# Connectors.net
KiCad netlist of a schematic drawn in Altium Designer
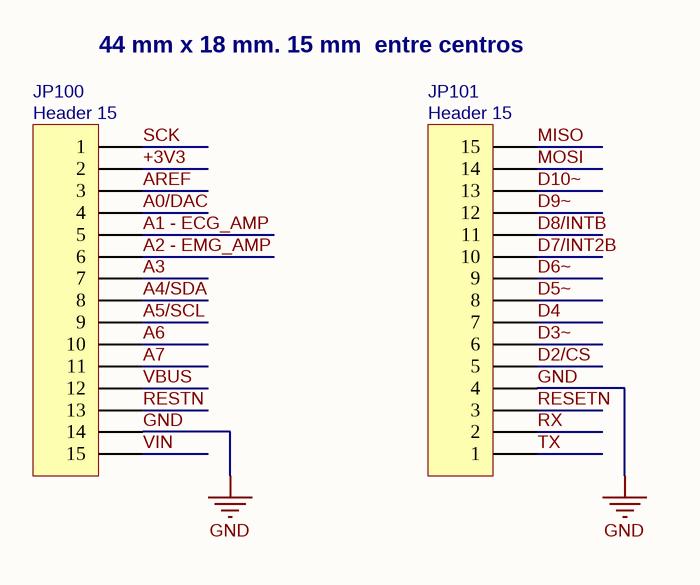
[diagram p0: Connectors.SchDoc]

(export (version "E")
  (design (tool "Eeschema 10.0.6"))
  (components
    (comp (ref "JP100")
      (value "Header 15")
      (footprint "HDR1X15")
      (description "Header, 15-Pin")
      (fields (field (name "PUBLISHER") "Altium Limited"))
      (libsource (lib "Miscellaneous Connectors") (part "Header 15"))
    )
    (comp (ref "JP101")
      (value "Header 15")
      (footprint "HDR1X15")
      (description "Header, 15-Pin")
      (fields (field (name "PUBLISHER") "Altium Limited"))
      (libsource (lib "") (part "Header 15_1"))
    )
  )
  (nets
    (net (code "1") (name "/+3V3") (class "Default")
      (node (ref "JP100") (pin "2") (pinfunction "2_2") (pintype "passive"))
    )
    (net (code "2") (name "/A0{slash}DAC") (class "Default")
      (node (ref "JP100") (pin "4") (pinfunction "4_4") (pintype "passive"))
    )
    (net (code "3") (name "/A1 - ECG_AMP") (class "Default")
      (node (ref "JP100") (pin "5") (pinfunction "5_5") (pintype "passive"))
    )
    (net (code "4") (name "/A2 - EMG_AMP") (class "Default")
      (node (ref "JP100") (pin "6") (pinfunction "6_6") (pintype "passive"))
    )
    (net (code "5") (name "/A3") (class "Default")
      (node (ref "JP100") (pin "7") (pinfunction "7_7") (pintype "passive"))
    )
    (net (code "6") (name "/A4{slash}SDA") (class "Default")
      (node (ref "JP100") (pin "8") (pinfunction "8_8") (pintype "passive"))
    )
    (net (code "7") (name "/A5{slash}SCL") (class "Default")
      (node (ref "JP100") (pin "9") (pinfunction "9_9") (pintype "passive"))
    )
    (net (code "8") (name "/A6") (class "Default")
      (node (ref "JP100") (pin "10") (pinfunction "10_10") (pintype "passive"))
    )
    (net (code "9") (name "/A7") (class "Default")
      (node (ref "JP100") (pin "11") (pinfunction "11_11") (pintype "passive"))
    )
    (net (code "10") (name "/AREF") (class "Default")
      (node (ref "JP100") (pin "3") (pinfunction "3_3") (pintype "passive"))
    )
    (net (code "11") (name "/D2{slash}CS") (class "Default")
      (node (ref "JP101") (pin "5") (pinfunction "5_5") (pintype "passive"))
    )
    (net (code "12") (name "/D3~") (class "Default")
      (node (ref "JP101") (pin "6") (pinfunction "6_6") (pintype "passive"))
    )
    (net (code "13") (name "/D4") (class "Default")
      (node (ref "JP101") (pin "7") (pinfunction "7_7") (pintype "passive"))
    )
    (net (code "14") (name "/D5~") (class "Default")
      (node (ref "JP101") (pin "8") (pinfunction "8_8") (pintype "passive"))
    )
    (net (code "15") (name "/D6~") (class "Default")
      (node (ref "JP101") (pin "9") (pinfunction "9_9") (pintype "passive"))
    )
    (net (code "16") (name "/D7{slash}INT2B") (class "Default")
      (node (ref "JP101") (pin "10") (pinfunction "10_10") (pintype "passive"))
    )
    (net (code "17") (name "/D8{slash}INTB") (class "Default")
      (node (ref "JP101") (pin "11") (pinfunction "11_11") (pintype "passive"))
    )
    (net (code "18") (name "/D9~") (class "Default")
      (node (ref "JP101") (pin "12") (pinfunction "12_12") (pintype "passive"))
    )
    (net (code "19") (name "/D10~") (class "Default")
      (node (ref "JP101") (pin "13") (pinfunction "13_13") (pintype "passive"))
    )
    (net (code "20") (name "/MISO") (class "Default")
      (node (ref "JP101") (pin "15") (pinfunction "15_15") (pintype "passive"))
    )
    (net (code "21") (name "/MOSI") (class "Default")
      (node (ref "JP101") (pin "14") (pinfunction "14_14") (pintype "passive"))
    )
    (net (code "22") (name "/RESETN") (class "Default")
      (node (ref "JP101") (pin "3") (pinfunction "3_3") (pintype "passive"))
    )
    (net (code "23") (name "/RESTN") (class "Default")
      (node (ref "JP100") (pin "13") (pinfunction "13_13") (pintype "passive"))
    )
    (net (code "24") (name "/RX") (class "Default")
      (node (ref "JP101") (pin "2") (pinfunction "2_2") (pintype "passive"))
    )
    (net (code "25") (name "/SCK") (class "Default")
      (node (ref "JP100") (pin "1") (pinfunction "1_1") (pintype "passive"))
    )
    (net (code "26") (name "/TX") (class "Default")
      (node (ref "JP101") (pin "1") (pinfunction "1_1") (pintype "passive"))
    )
    (net (code "27") (name "/VBUS") (class "Default")
      (node (ref "JP100") (pin "12") (pinfunction "12_12") (pintype "passive"))
    )
    (net (code "28") (name "/VIN") (class "Default")
      (node (ref "JP100") (pin "15") (pinfunction "15_15") (pintype "passive"))
    )
    (net (code "29") (name "GND") (class "Default")
      (node (ref "JP100") (pin "14") (pinfunction "14_14") (pintype "passive"))
      (node (ref "JP101") (pin "4") (pinfunction "4_4") (pintype "passive"))
    )
  )
)
